# untitled.net
KiCad netlist of a schematic drawn in EAGLE
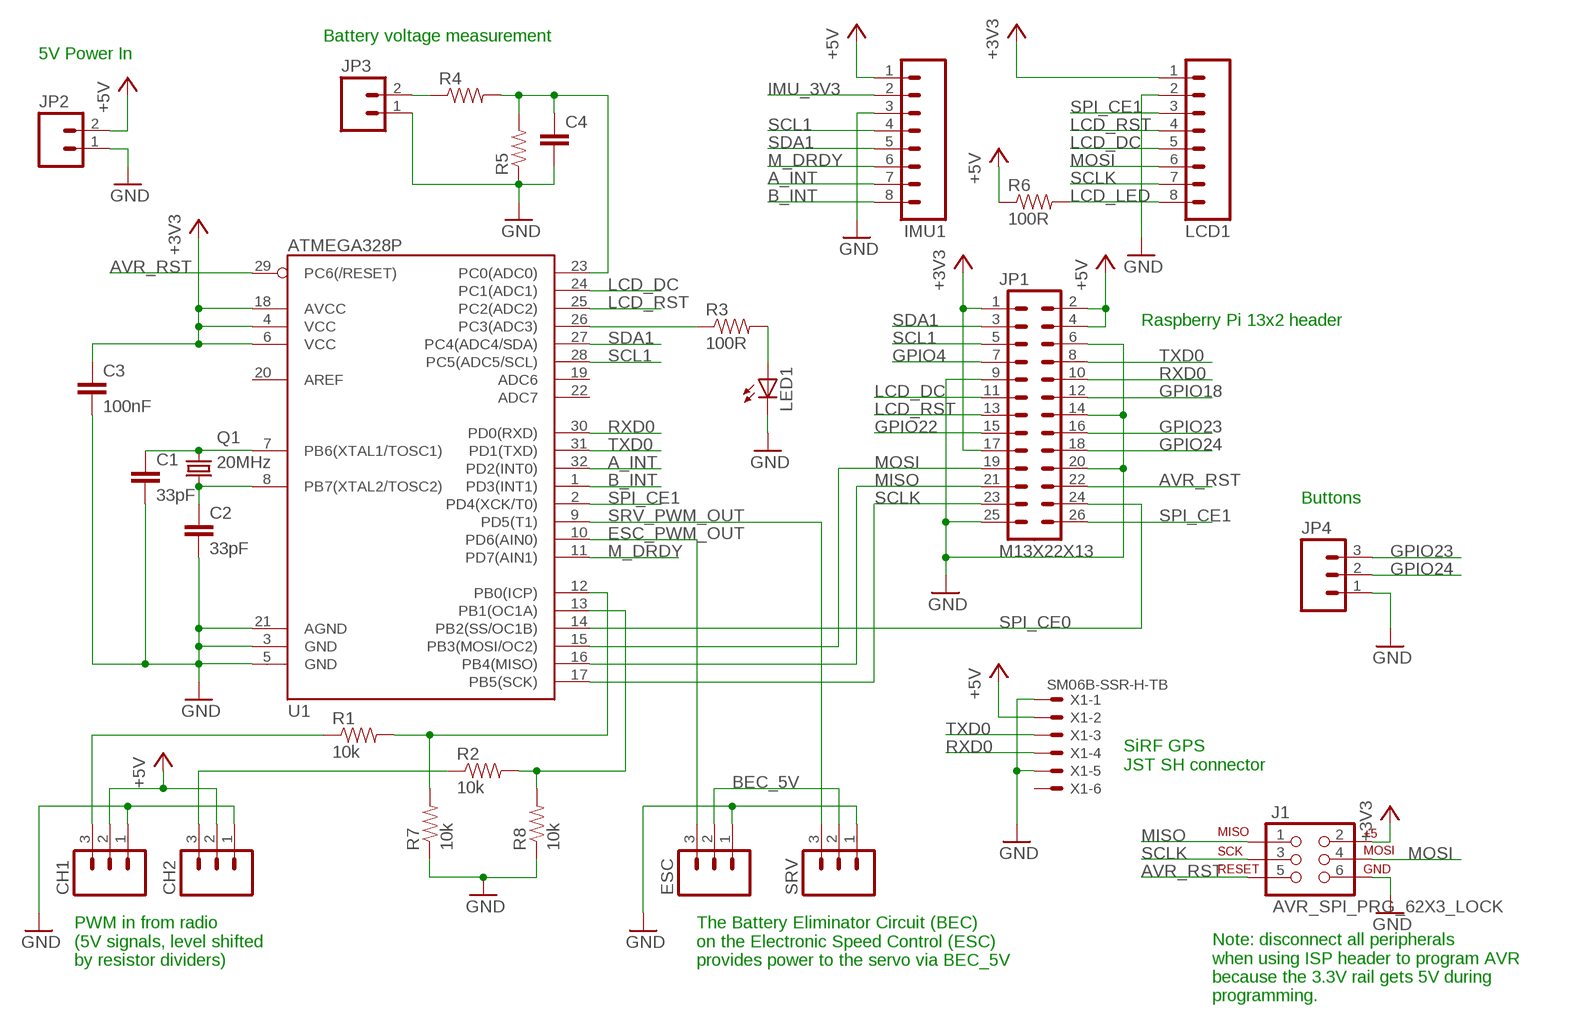
[diagram p0: schematic, sheet 1]

(export (version "E")
  (design (tool "Eeschema 10.0.6"))
  (components
    (comp (ref "C1")
      (value "33pF")
      (footprint "eagle-import:0805")
      (libsource (lib "eagle-import") (part "CAP0805"))
    )
    (comp (ref "C2")
      (value "33pF")
      (footprint "eagle-import:0805")
      (libsource (lib "eagle-import") (part "CAP0805"))
    )
    (comp (ref "C3")
      (value "100nF")
      (footprint "eagle-import:0805")
      (libsource (lib "eagle-import") (part "SparkFun-Passives_CAP0805"))
    )
    (comp (ref "C4")
      (value "CAP0805")
      (footprint "eagle-import:0805")
      (libsource (lib "eagle-import") (part "CAP0805"))
    )
    (comp (ref "CH1")
      (value "M03LOCK")
      (footprint "eagle-import:1X03_LOCK")
      (libsource (lib "eagle-import") (part "M03LOCK"))
    )
    (comp (ref "CH2")
      (value "M03LOCK")
      (footprint "eagle-import:1X03_LOCK")
      (libsource (lib "eagle-import") (part "M03LOCK"))
    )
    (comp (ref "ESC")
      (value "M03LOCK")
      (footprint "eagle-import:1X03_LOCK")
      (libsource (lib "eagle-import") (part "M03LOCK"))
    )
    (comp (ref "IMU1")
      (value "M08LOCK")
      (footprint "eagle-import:1X08_LOCK")
      (libsource (lib "eagle-import") (part "M08LOCK"))
    )
    (comp (ref "J1")
      (value "AVR_SPI_PRG_62X3_LOCK")
      (footprint "eagle-import:2X3_LOCK")
      (libsource (lib "eagle-import") (part "AVR_SPI_PRG_62X3_LOCK"))
    )
    (comp (ref "JP1")
      (value "M13X22X13")
      (footprint "eagle-import:2X13")
      (libsource (lib "eagle-import") (part "M13X22X13"))
    )
    (comp (ref "JP2")
      (value "M02POLAR_LOCK")
      (footprint "eagle-import:MOLEX-1X2_LOCK")
      (libsource (lib "eagle-import") (part "M02POLAR_LOCK"))
    )
    (comp (ref "JP3")
      (value "M02POLAR_LOCK")
      (footprint "eagle-import:MOLEX-1X2_LOCK")
      (libsource (lib "eagle-import") (part "M02POLAR_LOCK"))
    )
    (comp (ref "JP4")
      (value "M03POLAR_LOCK")
      (footprint "eagle-import:MOLEX-1X3_LOCK")
      (libsource (lib "eagle-import") (part "M03POLAR_LOCK"))
    )
    (comp (ref "LCD1")
      (value "M08LOCK")
      (footprint "eagle-import:1X08_LOCK")
      (libsource (lib "eagle-import") (part "M08LOCK"))
    )
    (comp (ref "LED1")
      (value "LED3MM")
      (footprint "eagle-import:LED3MM")
      (libsource (lib "eagle-import") (part "LED3MM"))
    )
    (comp (ref "Q1")
      (value "20MHz")
      (footprint "eagle-import:SM49")
      (libsource (lib "eagle-import") (part "CRYSTALSM49"))
    )
    (comp (ref "R1")
      (value "10k")
      (footprint "eagle-import:0805")
      (libsource (lib "eagle-import") (part "RESISTOR0805-RES"))
    )
    (comp (ref "R2")
      (value "10k")
      (footprint "eagle-import:0805")
      (libsource (lib "eagle-import") (part "RESISTOR0805-RES"))
    )
    (comp (ref "R3")
      (value "100R")
      (footprint "eagle-import:0805")
      (libsource (lib "eagle-import") (part "RESISTOR0805-RES"))
    )
    (comp (ref "R4")
      (value "RESISTOR0805-RES")
      (footprint "eagle-import:0805")
      (libsource (lib "eagle-import") (part "RESISTOR0805-RES"))
    )
    (comp (ref "R5")
      (value "RESISTOR0805-RES")
      (footprint "eagle-import:0805")
      (libsource (lib "eagle-import") (part "RESISTOR0805-RES"))
    )
    (comp (ref "R6")
      (value "100R")
      (footprint "eagle-import:0805")
      (libsource (lib "eagle-import") (part "RESISTOR0805-RES"))
    )
    (comp (ref "R7")
      (value "10k")
      (footprint "eagle-import:0805")
      (libsource (lib "eagle-import") (part "RESISTOR0805-RES"))
    )
    (comp (ref "R8")
      (value "10k")
      (footprint "eagle-import:0805")
      (libsource (lib "eagle-import") (part "RESISTOR0805-RES"))
    )
    (comp (ref "SRV")
      (value "M03LOCK")
      (footprint "eagle-import:1X03_LOCK")
      (libsource (lib "eagle-import") (part "M03LOCK"))
    )
    (comp (ref "U1")
      (value "ATMEGA328P")
      (footprint "eagle-import:TQFP32-08")
      (libsource (lib "eagle-import") (part "ATMEGA328_SMT"))
    )
    (comp (ref "X1")
      (value "SM06B-SSR-H-TB")
      (footprint "eagle-import:SM06B-SSR-H-TB")
      (libsource (lib "eagle-import") (part "SM06B-SSR-H-TB"))
    )
  )
  (nets
    (net (code "1") (name "+3V3") (class "Default")
      (node (ref "C3") (pin "1") (pinfunction "1_1") (pintype "passive"))
      (node (ref "J1") (pin "2") (pinfunction "2_2") (pintype "passive"))
      (node (ref "JP1") (pin "1") (pinfunction "1_1") (pintype "passive"))
      (node (ref "JP1") (pin "17") (pinfunction "17_17") (pintype "passive"))
      (node (ref "LCD1") (pin "1") (pinfunction "1_1") (pintype "passive"))
      (node (ref "U1") (pin "18") (pinfunction "AVCC_18") (pintype "bidirectional"))
      (node (ref "U1") (pin "4") (pinfunction "VCC_4") (pintype "bidirectional"))
      (node (ref "U1") (pin "6") (pinfunction "VCC_6") (pintype "bidirectional"))
    )
    (net (code "2") (name "+5V") (class "Default")
      (node (ref "CH1") (pin "2") (pinfunction "2_2") (pintype "passive"))
      (node (ref "CH2") (pin "2") (pinfunction "2_2") (pintype "passive"))
      (node (ref "IMU1") (pin "1") (pinfunction "1_1") (pintype "passive"))
      (node (ref "JP1") (pin "2") (pinfunction "2_2") (pintype "passive"))
      (node (ref "JP1") (pin "4") (pinfunction "4_4") (pintype "passive"))
      (node (ref "JP2") (pin "2") (pinfunction "2_2") (pintype "passive"))
      (node (ref "R6") (pin "1") (pinfunction "1_1") (pintype "passive"))
      (node (ref "X1") (pin "2") (pinfunction "S_2") (pintype "passive"))
    )
    (net (code "3") (name "/AVR_RST") (class "Default")
      (node (ref "J1") (pin "5") (pinfunction "5_5") (pintype "passive"))
      (node (ref "JP1") (pin "22") (pinfunction "22_22") (pintype "passive"))
      (node (ref "U1") (pin "29") (pinfunction "PC6(/RESET)_29") (pintype "bidirectional"))
    )
    (net (code "4") (name "/A_INT") (class "Default")
      (node (ref "IMU1") (pin "7") (pinfunction "7_7") (pintype "passive"))
      (node (ref "U1") (pin "32") (pinfunction "PD2(INT0)_32") (pintype "bidirectional"))
    )
    (net (code "5") (name "/BEC_5V") (class "Default")
      (node (ref "ESC") (pin "2") (pinfunction "2_2") (pintype "passive"))
      (node (ref "SRV") (pin "2") (pinfunction "2_2") (pintype "passive"))
    )
    (net (code "6") (name "/B_INT") (class "Default")
      (node (ref "IMU1") (pin "8") (pinfunction "8_8") (pintype "passive"))
      (node (ref "U1") (pin "1") (pinfunction "PD3(INT1)_1") (pintype "bidirectional"))
    )
    (net (code "7") (name "/ESC_PWM_OUT") (class "Default")
      (node (ref "ESC") (pin "3") (pinfunction "3_3") (pintype "passive"))
      (node (ref "U1") (pin "10") (pinfunction "PD6(AIN0)_10") (pintype "bidirectional"))
    )
    (net (code "8") (name "/GPIO4") (class "Default")
      (node (ref "JP1") (pin "7") (pinfunction "7_7") (pintype "passive"))
    )
    (net (code "9") (name "/GPIO18") (class "Default")
      (node (ref "JP1") (pin "12") (pinfunction "12_12") (pintype "passive"))
    )
    (net (code "10") (name "/GPIO22") (class "Default")
      (node (ref "JP1") (pin "15") (pinfunction "15_15") (pintype "passive"))
    )
    (net (code "11") (name "/GPIO23") (class "Default")
      (node (ref "JP1") (pin "16") (pinfunction "16_16") (pintype "passive"))
      (node (ref "JP4") (pin "3") (pinfunction "3_3") (pintype "passive"))
    )
    (net (code "12") (name "/GPIO24") (class "Default")
      (node (ref "JP1") (pin "18") (pinfunction "18_18") (pintype "passive"))
      (node (ref "JP4") (pin "2") (pinfunction "2_2") (pintype "passive"))
    )
    (net (code "13") (name "/IMU_3V3") (class "Default")
      (node (ref "IMU1") (pin "2") (pinfunction "2_2") (pintype "passive"))
    )
    (net (code "14") (name "/LCD_DC") (class "Default")
      (node (ref "JP1") (pin "11") (pinfunction "11_11") (pintype "passive"))
      (node (ref "LCD1") (pin "5") (pinfunction "5_5") (pintype "passive"))
      (node (ref "U1") (pin "24") (pinfunction "PC1(ADC1)_24") (pintype "bidirectional"))
    )
    (net (code "15") (name "/LCD_LED") (class "Default")
      (node (ref "LCD1") (pin "8") (pinfunction "8_8") (pintype "passive"))
      (node (ref "R6") (pin "2") (pinfunction "2_2") (pintype "passive"))
    )
    (net (code "16") (name "/LCD_RST") (class "Default")
      (node (ref "JP1") (pin "13") (pinfunction "13_13") (pintype "passive"))
      (node (ref "LCD1") (pin "4") (pinfunction "4_4") (pintype "passive"))
      (node (ref "U1") (pin "25") (pinfunction "PC2(ADC2)_25") (pintype "bidirectional"))
    )
    (net (code "17") (name "/MISO") (class "Default")
      (node (ref "J1") (pin "1") (pinfunction "1_1") (pintype "passive"))
      (node (ref "JP1") (pin "21") (pinfunction "21_21") (pintype "passive"))
      (node (ref "U1") (pin "16") (pinfunction "PB4(MISO)_16") (pintype "bidirectional"))
    )
    (net (code "18") (name "/MOSI") (class "Default")
      (node (ref "J1") (pin "4") (pinfunction "4_4") (pintype "passive"))
      (node (ref "JP1") (pin "19") (pinfunction "19_19") (pintype "passive"))
      (node (ref "LCD1") (pin "6") (pinfunction "6_6") (pintype "passive"))
      (node (ref "U1") (pin "15") (pinfunction "PB3(MOSI/OC2)_15") (pintype "bidirectional"))
    )
    (net (code "19") (name "/M_DRDY") (class "Default")
      (node (ref "IMU1") (pin "6") (pinfunction "6_6") (pintype "passive"))
      (node (ref "U1") (pin "11") (pinfunction "PD7(AIN1)_11") (pintype "bidirectional"))
    )
    (net (code "20") (name "/RXD0") (class "Default")
      (node (ref "JP1") (pin "10") (pinfunction "10_10") (pintype "passive"))
      (node (ref "U1") (pin "30") (pinfunction "PD0(RXD)_30") (pintype "bidirectional"))
      (node (ref "X1") (pin "4") (pinfunction "S_4") (pintype "passive"))
    )
    (net (code "21") (name "/SCL1") (class "Default")
      (node (ref "IMU1") (pin "4") (pinfunction "4_4") (pintype "passive"))
      (node (ref "JP1") (pin "5") (pinfunction "5_5") (pintype "passive"))
      (node (ref "U1") (pin "28") (pinfunction "PC5(ADC5/SCL)_28") (pintype "bidirectional"))
    )
    (net (code "22") (name "/SCLK") (class "Default")
      (node (ref "J1") (pin "3") (pinfunction "3_3") (pintype "passive"))
      (node (ref "JP1") (pin "23") (pinfunction "23_23") (pintype "passive"))
      (node (ref "LCD1") (pin "7") (pinfunction "7_7") (pintype "passive"))
      (node (ref "U1") (pin "17") (pinfunction "PB5(SCK)_17") (pintype "bidirectional"))
    )
    (net (code "23") (name "/SDA1") (class "Default")
      (node (ref "IMU1") (pin "5") (pinfunction "5_5") (pintype "passive"))
      (node (ref "JP1") (pin "3") (pinfunction "3_3") (pintype "passive"))
      (node (ref "U1") (pin "27") (pinfunction "PC4(ADC4/SDA)_27") (pintype "bidirectional"))
    )
    (net (code "24") (name "/SPI_CE0") (class "Default")
      (node (ref "JP1") (pin "24") (pinfunction "24_24") (pintype "passive"))
      (node (ref "U1") (pin "14") (pinfunction "PB2(SS/OC1B)_14") (pintype "bidirectional"))
    )
    (net (code "25") (name "/SPI_CE1") (class "Default")
      (node (ref "JP1") (pin "26") (pinfunction "26_26") (pintype "passive"))
      (node (ref "LCD1") (pin "3") (pinfunction "3_3") (pintype "passive"))
      (node (ref "U1") (pin "2") (pinfunction "PD4(XCK/T0)_2") (pintype "bidirectional"))
    )
    (net (code "26") (name "/SRV_PWM_OUT") (class "Default")
      (node (ref "SRV") (pin "3") (pinfunction "3_3") (pintype "passive"))
      (node (ref "U1") (pin "9") (pinfunction "PD5(T1)_9") (pintype "bidirectional"))
    )
    (net (code "27") (name "/TXD0") (class "Default")
      (node (ref "JP1") (pin "8") (pinfunction "8_8") (pintype "passive"))
      (node (ref "U1") (pin "31") (pinfunction "PD1(TXD)_31") (pintype "bidirectional"))
      (node (ref "X1") (pin "3") (pinfunction "S_3") (pintype "passive"))
    )
    (net (code "28") (name "GND") (class "Default")
      (node (ref "C1") (pin "2") (pinfunction "2_2") (pintype "passive"))
      (node (ref "C2") (pin "2") (pinfunction "2_2") (pintype "passive"))
      (node (ref "C3") (pin "2") (pinfunction "2_2") (pintype "passive"))
      (node (ref "C4") (pin "2") (pinfunction "2_2") (pintype "passive"))
      (node (ref "CH1") (pin "1") (pinfunction "1_1") (pintype "passive"))
      (node (ref "CH2") (pin "1") (pinfunction "1_1") (pintype "passive"))
      (node (ref "ESC") (pin "1") (pinfunction "1_1") (pintype "passive"))
      (node (ref "IMU1") (pin "3") (pinfunction "3_3") (pintype "passive"))
      (node (ref "J1") (pin "6") (pinfunction "6_6") (pintype "passive"))
      (node (ref "JP1") (pin "14") (pinfunction "14_14") (pintype "passive"))
      (node (ref "JP1") (pin "20") (pinfunction "20_20") (pintype "passive"))
      (node (ref "JP1") (pin "25") (pinfunction "25_25") (pintype "passive"))
      (node (ref "JP1") (pin "6") (pinfunction "6_6") (pintype "passive"))
      (node (ref "JP1") (pin "9") (pinfunction "9_9") (pintype "passive"))
      (node (ref "JP2") (pin "1") (pinfunction "1_1") (pintype "passive"))
      (node (ref "JP3") (pin "1") (pinfunction "1_1") (pintype "passive"))
      (node (ref "JP4") (pin "1") (pinfunction "1_1") (pintype "passive"))
      (node (ref "LCD1") (pin "2") (pinfunction "2_2") (pintype "passive"))
      (node (ref "LED1") (pin "K") (pinfunction "C_K") (pintype "passive"))
      (node (ref "R5") (pin "1") (pinfunction "1_1") (pintype "passive"))
      (node (ref "R7") (pin "1") (pinfunction "1_1") (pintype "passive"))
      (node (ref "R8") (pin "1") (pinfunction "1_1") (pintype "passive"))
      (node (ref "SRV") (pin "1") (pinfunction "1_1") (pintype "passive"))
      (node (ref "U1") (pin "21") (pinfunction "AGND_21") (pintype "bidirectional"))
      (node (ref "U1") (pin "3") (pinfunction "GND_3") (pintype "bidirectional"))
      (node (ref "U1") (pin "5") (pinfunction "GND_5") (pintype "bidirectional"))
      (node (ref "X1") (pin "1") (pinfunction "S_1") (pintype "passive"))
      (node (ref "X1") (pin "5") (pinfunction "S_5") (pintype "passive"))
    )
    (net (code "29") (name "Net-(CH1-Pad3)") (class "Default")
      (node (ref "CH1") (pin "3") (pinfunction "3_3") (pintype "passive"))
      (node (ref "R1") (pin "1") (pinfunction "1_1") (pintype "passive"))
    )
    (net (code "30") (name "Net-(CH2-Pad3)") (class "Default")
      (node (ref "CH2") (pin "3") (pinfunction "3_3") (pintype "passive"))
      (node (ref "R2") (pin "1") (pinfunction "1_1") (pintype "passive"))
    )
    (net (code "31") (name "Net-(JP3-Pad2)") (class "Default")
      (node (ref "JP3") (pin "2") (pinfunction "2_2") (pintype "passive"))
      (node (ref "R4") (pin "1") (pinfunction "1_1") (pintype "passive"))
    )
    (net (code "32") (name "Net-(LED1-PadA)") (class "Default")
      (node (ref "LED1") (pin "A") (pinfunction "A_A") (pintype "passive"))
      (node (ref "R3") (pin "2") (pinfunction "2_2") (pintype "passive"))
    )
    (net (code "33") (name "Net-(U1-PB0(ICP))") (class "Default")
      (node (ref "R1") (pin "2") (pinfunction "2_2") (pintype "passive"))
      (node (ref "R7") (pin "2") (pinfunction "2_2") (pintype "passive"))
      (node (ref "U1") (pin "12") (pinfunction "PB0(ICP)_12") (pintype "bidirectional"))
    )
    (net (code "34") (name "Net-(U1-PB1(OC1A))") (class "Default")
      (node (ref "R2") (pin "2") (pinfunction "2_2") (pintype "passive"))
      (node (ref "R8") (pin "2") (pinfunction "2_2") (pintype "passive"))
      (node (ref "U1") (pin "13") (pinfunction "PB1(OC1A)_13") (pintype "bidirectional"))
    )
    (net (code "35") (name "Net-(U1-PB6(XTAL1{slash}TOSC1))") (class "Default")
      (node (ref "C1") (pin "1") (pinfunction "1_1") (pintype "passive"))
      (node (ref "Q1") (pin "1") (pinfunction "1_1") (pintype "passive"))
      (node (ref "U1") (pin "7") (pinfunction "PB6(XTAL1/TOSC1)_7") (pintype "bidirectional"))
    )
    (net (code "36") (name "Net-(U1-PB7(XTAL2{slash}TOSC2))") (class "Default")
      (node (ref "C2") (pin "1") (pinfunction "1_1") (pintype "passive"))
      (node (ref "Q1") (pin "2") (pinfunction "2_2") (pintype "passive"))
      (node (ref "U1") (pin "8") (pinfunction "PB7(XTAL2/TOSC2)_8") (pintype "bidirectional"))
    )
    (net (code "37") (name "Net-(U1-PC0(ADC0))") (class "Default")
      (node (ref "C4") (pin "1") (pinfunction "1_1") (pintype "passive"))
      (node (ref "R4") (pin "2") (pinfunction "2_2") (pintype "passive"))
      (node (ref "R5") (pin "2") (pinfunction "2_2") (pintype "passive"))
      (node (ref "U1") (pin "23") (pinfunction "PC0(ADC0)_23") (pintype "bidirectional"))
    )
    (net (code "38") (name "Net-(U1-PC3(ADC3))") (class "Default")
      (node (ref "R3") (pin "1") (pinfunction "1_1") (pintype "passive"))
      (node (ref "U1") (pin "26") (pinfunction "PC3(ADC3)_26") (pintype "bidirectional"))
    )
    (net (code "39") (name "unconnected-(U1-ADC6-Pad19)") (class "Default")
      (node (ref "U1") (pin "19") (pinfunction "ADC6_19") (pintype "bidirectional"))
    )
    (net (code "40") (name "unconnected-(U1-ADC7-Pad22)") (class "Default")
      (node (ref "U1") (pin "22") (pinfunction "ADC7_22") (pintype "bidirectional"))
    )
    (net (code "41") (name "unconnected-(U1-AREF-Pad20)") (class "Default")
      (node (ref "U1") (pin "20") (pinfunction "AREF_20") (pintype "bidirectional"))
    )
    (net (code "42") (name "unconnected-(X1F-S-Pad6)") (class "Default")
      (node (ref "X1") (pin "6") (pinfunction "S_6") (pintype "passive"))
    )
  )
)
